# MQTT_SelService_V2.net
KiCad netlist of a schematic drawn in Altium Designer
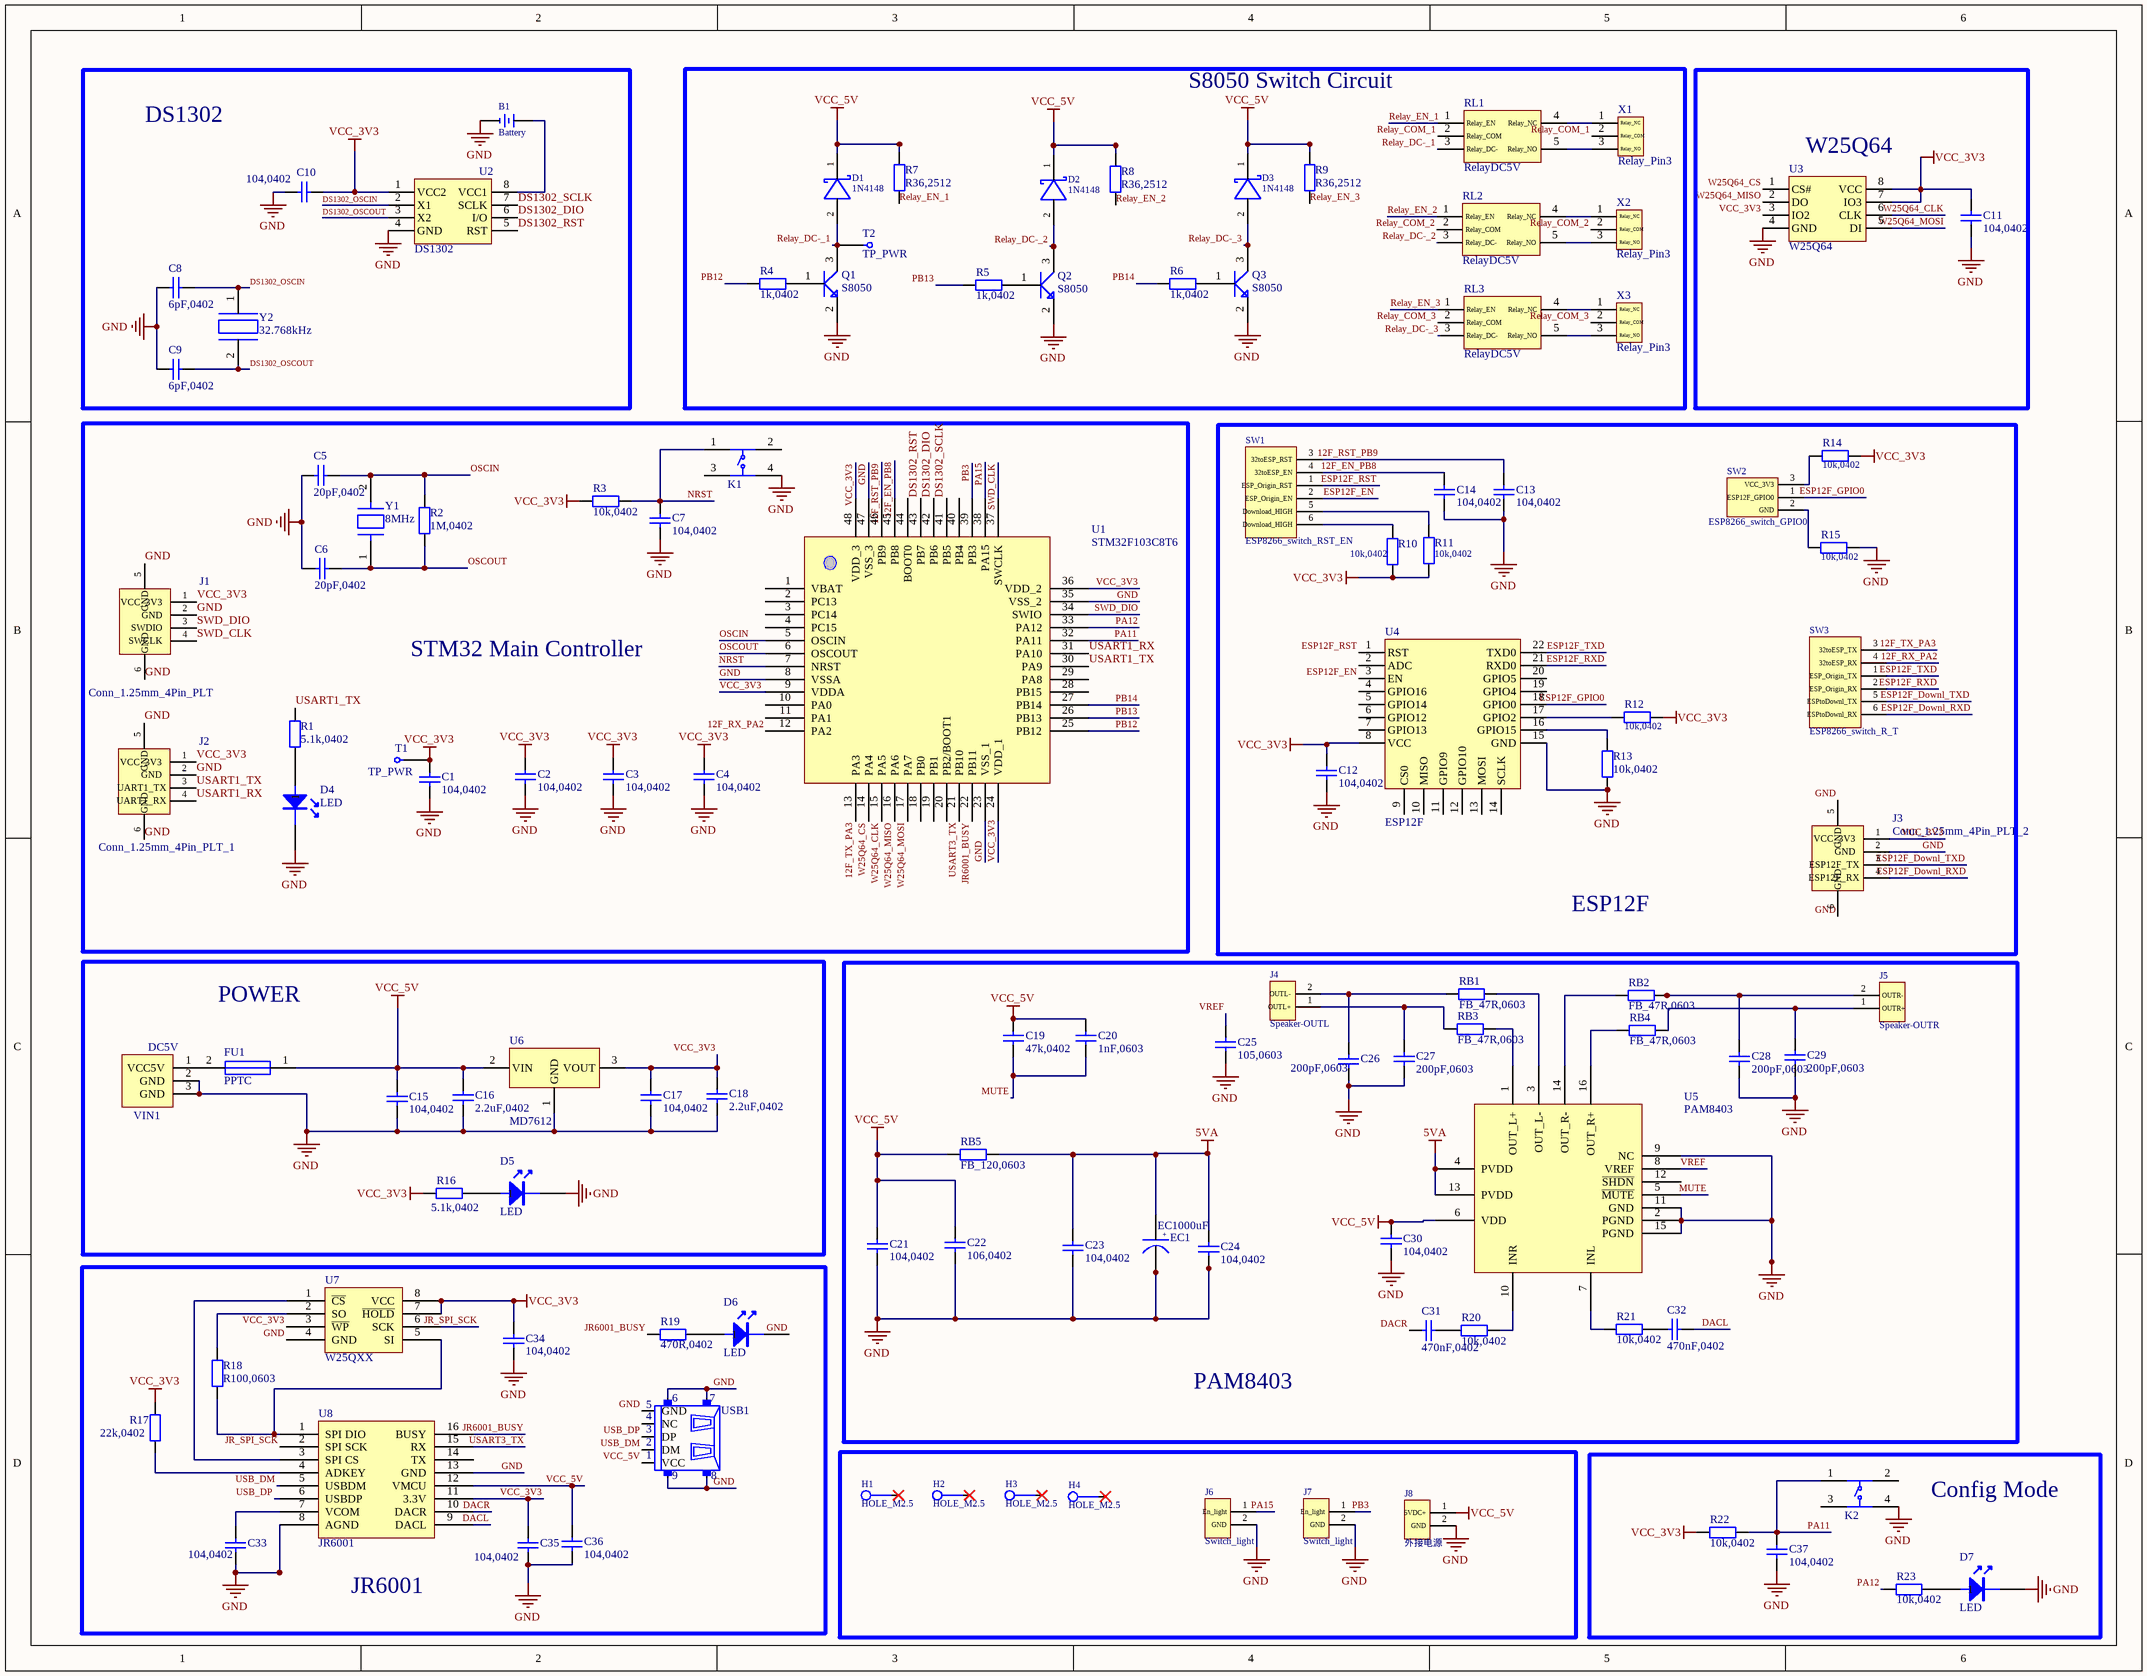
[diagram p0: MQTT_SelService_V2.SchDoc]

(export (version "E")
  (design (tool "Eeschema 10.0.6"))
  (components
    (comp (ref "B1")
      (value "Battery")
      (footprint "Battery")
      (description "V_Backup")
      (libsource (lib "MQTT_SelService_V1") (part "Battery"))
    )
    (comp (ref "C1")
      (value "104,0402")
      (footprint "C0402")
      (fields (field (name "PUBLISHER") "Altium Limited"))
      (libsource (lib "MQTT_SelService_V1") (part "Cap1"))
    )
    (comp (ref "C2")
      (value "104,0402")
      (footprint "C0402")
      (fields (field (name "PUBLISHER") "Altium Limited"))
      (libsource (lib "MQTT_SelService_V1") (part "Cap1"))
    )
    (comp (ref "C3")
      (value "104,0402")
      (footprint "C0402")
      (fields (field (name "PUBLISHER") "Altium Limited"))
      (libsource (lib "MQTT_SelService_V1") (part "Cap1"))
    )
    (comp (ref "C4")
      (value "104,0402")
      (footprint "C0402")
      (fields (field (name "PUBLISHER") "Altium Limited"))
      (libsource (lib "MQTT_SelService_V1") (part "Cap1"))
    )
    (comp (ref "C5")
      (value "20pF,0402")
      (footprint "C0402")
      (fields (field (name "PUBLISHER") "Altium Limited"))
      (libsource (lib "MQTT_SelService_V1") (part "Cap0402_3"))
    )
    (comp (ref "C6")
      (value "20pF,0402")
      (footprint "C0402")
      (fields (field (name "PUBLISHER") "Altium Limited"))
      (libsource (lib "MQTT_SelService_V1") (part "Cap0402_3"))
    )
    (comp (ref "C7")
      (value "104,0402")
      (footprint "C0402")
      (fields (field (name "PUBLISHER") "Altium Limited"))
      (libsource (lib "MQTT_SelService_V1") (part "Cap1"))
    )
    (comp (ref "C8")
      (value "6pF,0402")
      (footprint "C0402")
      (fields (field (name "PUBLISHER") "Altium Limited"))
      (libsource (lib "MQTT_SelService_V1") (part "Cap0402_2"))
    )
    (comp (ref "C9")
      (value "6pF,0402")
      (footprint "C0402")
      (fields (field (name "PUBLISHER") "Altium Limited"))
      (libsource (lib "MQTT_SelService_V1") (part "Cap0402_2"))
    )
    (comp (ref "C10")
      (value "104,0402")
      (footprint "C0402")
      (fields (field (name "PUBLISHER") "Altium Limited"))
      (libsource (lib "MQTT_SelService_V1") (part "Cap1"))
    )
    (comp (ref "C11")
      (value "104,0402")
      (footprint "C0402")
      (fields (field (name "PUBLISHER") "Altium Limited"))
      (libsource (lib "MQTT_SelService_V1") (part "Cap1"))
    )
    (comp (ref "C12")
      (value "104,0402")
      (footprint "C0402")
      (fields (field (name "PUBLISHER") "Altium Limited"))
      (libsource (lib "MQTT_SelService_V1") (part "Cap1"))
    )
    (comp (ref "C13")
      (value "104,0402")
      (footprint "C0402")
      (fields (field (name "PUBLISHER") "Altium Limited"))
      (libsource (lib "MQTT_SelService_V1") (part "Cap1"))
    )
    (comp (ref "C14")
      (value "104,0402")
      (footprint "C0402")
      (fields (field (name "PUBLISHER") "Altium Limited"))
      (libsource (lib "MQTT_SelService_V1") (part "Cap1"))
    )
    (comp (ref "C15")
      (value "104,0402")
      (footprint "C0402")
      (fields (field (name "PUBLISHER") "Altium Limited"))
      (libsource (lib "MQTT_SelService_V1") (part "Cap1"))
    )
    (comp (ref "C16")
      (value "2.2uF,0402")
      (footprint "C0402")
      (fields (field (name "PUBLISHER") "Altium Limited"))
      (libsource (lib "MQTT_SelService_V1") (part "C2.2uF"))
    )
    (comp (ref "C17")
      (value "104,0402")
      (footprint "C0402")
      (fields (field (name "PUBLISHER") "Altium Limited"))
      (libsource (lib "MQTT_SelService_V1") (part "Cap1"))
    )
    (comp (ref "C18")
      (value "2.2uF,0402")
      (footprint "C0402")
      (fields (field (name "PUBLISHER") "Altium Limited"))
      (libsource (lib "MQTT_SelService_V1") (part "C2.2uF"))
    )
    (comp (ref "C19")
      (value "47k,0402")
      (footprint "C0402")
      (description "104,0402")
      (fields (field (name "PUBLISHER") "Altium Limited"))
      (libsource (lib "MQTT_SelService_V1") (part "Cap1"))
    )
    (comp (ref "C20")
      (value "1nF,0603")
      (footprint "C0603")
      (fields (field (name "PUBLISHER") "Altium Limited"))
      (libsource (lib "MQTT_SelService_V1") (part "C1nF"))
    )
    (comp (ref "C21")
      (value "104,0402")
      (footprint "C0402")
      (fields (field (name "PUBLISHER") "Altium Limited"))
      (libsource (lib "MQTT_SelService_V1") (part "Cap1"))
    )
    (comp (ref "C22")
      (value "106,0402")
      (footprint "C0402")
      (description "104,0402")
      (fields (field (name "PUBLISHER") "Altium Limited"))
      (libsource (lib "MQTT_SelService_V1") (part "Cap1"))
    )
    (comp (ref "C23")
      (value "104,0402")
      (footprint "C0402")
      (fields (field (name "PUBLISHER") "Altium Limited"))
      (libsource (lib "MQTT_SelService_V1") (part "Cap1"))
    )
    (comp (ref "C24")
      (value "104,0402")
      (footprint "C0402")
      (fields (field (name "PUBLISHER") "Altium Limited"))
      (libsource (lib "MQTT_SelService_V1") (part "Cap1"))
    )
    (comp (ref "C25")
      (value "105,0603")
      (footprint "C0603")
      (fields (field (name "PUBLISHER") "Altium Limited"))
      (libsource (lib "MQTT_SelService_V1") (part "Cap2"))
    )
    (comp (ref "C26")
      (value "200pF,0603")
      (footprint "C0603")
      (fields (field (name "PUBLISHER") "Altium Limited"))
      (libsource (lib "MQTT_SelService_V1") (part "C200pF"))
    )
    (comp (ref "C27")
      (value "200pF,0603")
      (footprint "C0603")
      (fields (field (name "PUBLISHER") "Altium Limited"))
      (libsource (lib "MQTT_SelService_V1") (part "C200pF"))
    )
    (comp (ref "C28")
      (value "200pF,0603")
      (footprint "C0603")
      (fields (field (name "PUBLISHER") "Altium Limited"))
      (libsource (lib "MQTT_SelService_V1") (part "C200pF"))
    )
    (comp (ref "C29")
      (value "200pF,0603")
      (footprint "C0603")
      (fields (field (name "PUBLISHER") "Altium Limited"))
      (libsource (lib "MQTT_SelService_V1") (part "C200pF"))
    )
    (comp (ref "C30")
      (value "104,0402")
      (footprint "C0402")
      (fields (field (name "PUBLISHER") "Altium Limited"))
      (libsource (lib "MQTT_SelService_V1") (part "Cap1"))
    )
    (comp (ref "C31")
      (value "470nF,0402")
      (footprint "C0402")
      (fields (field (name "PUBLISHER") "Altium Limited"))
      (libsource (lib "MQTT_SelService_V1") (part "C470nF"))
    )
    (comp (ref "C32")
      (value "470nF,0402")
      (footprint "C0402")
      (fields (field (name "PUBLISHER") "Altium Limited"))
      (libsource (lib "MQTT_SelService_V1") (part "C470nF"))
    )
    (comp (ref "C33")
      (value "104,0402")
      (footprint "C0402")
      (fields (field (name "PUBLISHER") "Altium Limited"))
      (libsource (lib "MQTT_SelService_V1") (part "Cap1"))
    )
    (comp (ref "C34")
      (value "104,0402")
      (footprint "C0402")
      (fields (field (name "PUBLISHER") "Altium Limited"))
      (libsource (lib "MQTT_SelService_V1") (part "Cap1"))
    )
    (comp (ref "C35")
      (value "104,0402")
      (footprint "C0402")
      (fields (field (name "PUBLISHER") "Altium Limited"))
      (libsource (lib "MQTT_SelService_V1") (part "Cap1"))
    )
    (comp (ref "C36")
      (value "104,0402")
      (footprint "C0402")
      (fields (field (name "PUBLISHER") "Altium Limited"))
      (libsource (lib "MQTT_SelService_V1") (part "Cap1"))
    )
    (comp (ref "C37")
      (value "104,0402")
      (footprint "C0402")
      (fields (field (name "PUBLISHER") "Altium Limited"))
      (libsource (lib "MQTT_SelService_V1") (part "Cap1"))
    )
    (comp (ref "D1")
      (value "1N4148")
      (footprint "1N4148")
      (description "SOD-123")
      (libsource (lib "MQTT_SelService_V1") (part "1N4148"))
    )
    (comp (ref "D2")
      (value "1N4148")
      (footprint "1N4148")
      (description "SOD-123")
      (libsource (lib "MQTT_SelService_V1") (part "1N4148"))
    )
    (comp (ref "D3")
      (value "1N4148")
      (footprint "1N4148")
      (description "SOD-123")
      (libsource (lib "MQTT_SelService_V1") (part "1N4148"))
    )
    (comp (ref "D4") (value "LED") (footprint "LED0603") (libsource (lib "MQTT_SelService_V1") (part "LED")))
    (comp (ref "D5") (value "LED") (footprint "LED0603") (libsource (lib "MQTT_SelService_V1") (part "LED")))
    (comp (ref "D6") (value "LED") (footprint "LED0603") (libsource (lib "MQTT_SelService_V1") (part "LED")))
    (comp (ref "D7") (value "LED") (footprint "LED0603") (libsource (lib "MQTT_SelService_V1") (part "LED")))
    (comp (ref "EC1")
      (value "EC1000uF")
      (footprint "EC1000uF")
      (description "1000uF")
      (libsource (lib "MQTT_SelService_V1") (part "EC"))
    )
    (comp (ref "FU1") (value "PPTC") (footprint "F0805") (libsource (lib "MQTT_SelService_V1") (part "PPTC")))
    (comp (ref "H1")
      (value "HOLE_M2.5")
      (footprint "hole")
      (libsource (lib "MQTT_SelService_V1") (part "HOLE_M2.5"))
    )
    (comp (ref "H2")
      (value "HOLE_M2.5")
      (footprint "hole")
      (libsource (lib "MQTT_SelService_V1") (part "HOLE_M2.5"))
    )
    (comp (ref "H3")
      (value "HOLE_M2.5")
      (footprint "hole")
      (libsource (lib "MQTT_SelService_V1") (part "HOLE_M2.5"))
    )
    (comp (ref "H4")
      (value "HOLE_M2.5")
      (footprint "hole")
      (libsource (lib "MQTT_SelService_V1") (part "HOLE_M2.5"))
    )
    (comp (ref "J1")
      (value "Conn_1.25mm_4Pin_PLT")
      (footprint "CONN-SMD_4P-P1.25_HCTL_HC-1.25-4PLT")
      (description "SWD_Conn")
      (libsource (lib "MQTT_SelService_V1") (part "Conn_1.25mm_4Pin_PLT"))
    )
    (comp (ref "J2")
      (value "Conn_1.25mm_4Pin_PLT_1")
      (footprint "CONN-SMD_4P-P1.25_HCTL_HC-1.25-4PLT")
      (description "USART_Conn")
      (libsource (lib "MQTT_SelService_V1") (part "Conn_1.25mm_4Pin_PLT_1"))
    )
    (comp (ref "J3")
      (value "Conn_1.25mm_4Pin_PLT_2")
      (footprint "CONN-SMD_4P-P1.25_HCTL_HC-1.25-4PLT")
      (description "ESP_Downl_Conn")
      (libsource (lib "MQTT_SelService_V1") (part "Conn_1.25mm_4Pin_PLT_2"))
    )
    (comp (ref "J4")
      (value "Speaker-OUTL")
      (footprint "XH_2.54mm_2Pin_直插")
      (libsource (lib "MQTT_SelService_V1") (part "Speaker-OUTL"))
    )
    (comp (ref "J5")
      (value "Speaker-OUTR")
      (footprint "XH_2.54mm_2Pin_直插")
      (libsource (lib "MQTT_SelService_V1") (part "Speaker-OUTR"))
    )
    (comp (ref "J6")
      (value "Switch_light")
      (footprint "XH_2.54mm_2Pin_直插")
      (description "2.54mm,直插")
      (libsource (lib "MQTT_SelService_V1") (part "Switch_light"))
    )
    (comp (ref "J7")
      (value "Switch_light")
      (footprint "XH_2.54mm_2Pin_直插")
      (description "2.54mm,直插")
      (libsource (lib "MQTT_SelService_V1") (part "Switch_light"))
    )
    (comp (ref "J8")
      (value "外接电源")
      (footprint "XH_2.54mm_2Pin_直插")
      (description "2.54mm")
      (libsource (lib "MQTT_SelService_V1") (part "外接电源"))
    )
    (comp (ref "K1")
      (value "TS665CJ")
      (footprint "SW-TH_4P-L6.0-W6.0-P4.50-LS6.5")
      (description "矩阵按键")
      (libsource (lib "MQTT_SelService_V1") (part "TS665CJ"))
    )
    (comp (ref "K2")
      (value "TS665CJ")
      (footprint "SW-TH_4P-L6.0-W6.0-P4.50-LS6.5")
      (description "矩阵按键")
      (libsource (lib "MQTT_SelService_V1") (part "TS665CJ"))
    )
    (comp (ref "Q1")
      (value "S8050")
      (footprint "S8050")
      (libsource (lib "MQTT_SelService_V1") (part "S8050"))
    )
    (comp (ref "Q2")
      (value "S8050")
      (footprint "S8050")
      (libsource (lib "MQTT_SelService_V1") (part "S8050"))
    )
    (comp (ref "Q3")
      (value "S8050")
      (footprint "S8050")
      (libsource (lib "MQTT_SelService_V1") (part "S8050"))
    )
    (comp (ref "R1")
      (value "5.1k,0402")
      (footprint "R0402")
      (description "10k,0402")
      (fields (field (name "PUBLISHER") "Altium Limited"))
      (libsource (lib "") (part "R10k_1"))
    )
    (comp (ref "R2")
      (value "1M,0402")
      (footprint "R0402")
      (fields (field (name "PUBLISHER") "Altium Limited"))
      (libsource (lib "MQTT_SelService_V1") (part "R1M"))
    )
    (comp (ref "R3")
      (value "10k,0402")
      (footprint "R0402")
      (description "10,0402")
      (fields (field (name "PUBLISHER") "Altium Limited"))
      (libsource (lib "") (part "R1M_1"))
    )
    (comp (ref "R4")
      (value "1k,0402")
      (footprint "R0402")
      (description "10k,0402")
      (fields (field (name "PUBLISHER") "Altium Limited"))
      (libsource (lib "MQTT_SelService_V1") (part "R10k"))
    )
    (comp (ref "R5")
      (value "1k,0402")
      (footprint "R0402")
      (description "10k,0402")
      (fields (field (name "PUBLISHER") "Altium Limited"))
      (libsource (lib "MQTT_SelService_V1") (part "R10k"))
    )
    (comp (ref "R6")
      (value "1k,0402")
      (footprint "R0402")
      (description "10k,0402")
      (fields (field (name "PUBLISHER") "Altium Limited"))
      (libsource (lib "MQTT_SelService_V1") (part "R10k"))
    )
    (comp (ref "R7")
      (value "R36,2512")
      (footprint "R2512")
      (fields (field (name "PUBLISHER") "Altium Limited"))
      (libsource (lib "MQTT_SelService_V1") (part "R36,2512"))
    )
    (comp (ref "R8")
      (value "R36,2512")
      (footprint "R2512")
      (fields (field (name "PUBLISHER") "Altium Limited"))
      (libsource (lib "MQTT_SelService_V1") (part "R36,2512"))
    )
    (comp (ref "R9")
      (value "R36,2512")
      (footprint "R2512")
      (fields (field (name "PUBLISHER") "Altium Limited"))
      (libsource (lib "MQTT_SelService_V1") (part "R36,2512"))
    )
    (comp (ref "R10")
      (value "10k,0402")
      (footprint "R0402")
      (fields (field (name "PUBLISHER") "Altium Limited"))
      (libsource (lib "") (part "R10k_1"))
    )
    (comp (ref "R11")
      (value "10k,0402")
      (footprint "R0402")
      (fields (field (name "PUBLISHER") "Altium Limited"))
      (libsource (lib "") (part "R10k_1"))
    )
    (comp (ref "R12")
      (value "10k,0402")
      (footprint "R0402")
      (fields (field (name "PUBLISHER") "Altium Limited"))
      (libsource (lib "MQTT_SelService_V1") (part "R10k"))
    )
    (comp (ref "R13")
      (value "10k,0402")
      (footprint "R0402")
      (fields (field (name "PUBLISHER") "Altium Limited"))
      (libsource (lib "") (part "R10k_1"))
    )
    (comp (ref "R14")
      (value "10k,0402")
      (footprint "R0402")
      (fields (field (name "PUBLISHER") "Altium Limited"))
      (libsource (lib "MQTT_SelService_V1") (part "R10k"))
    )
    (comp (ref "R15")
      (value "10k,0402")
      (footprint "R0402")
      (fields (field (name "PUBLISHER") "Altium Limited"))
      (libsource (lib "MQTT_SelService_V1") (part "R10k"))
    )
    (comp (ref "R16")
      (value "5.1k,0402")
      (footprint "R0402")
      (description "10k,0402")
      (fields (field (name "PUBLISHER") "Altium Limited"))
      (libsource (lib "MQTT_SelService_V1") (part "R10k"))
    )
    (comp (ref "R17")
      (value "22k,0402")
      (footprint "R0402")
      (fields (field (name "PUBLISHER") "Altium Limited"))
      (libsource (lib "MQTT_SelService_V1") (part "R22k"))
    )
    (comp (ref "R18")
      (value "R100,0603")
      (footprint "R0603")
      (description "0603")
      (fields (field (name "PUBLISHER") "Altium Limited"))
      (libsource (lib "MQTT_SelService_V1") (part "R100"))
    )
    (comp (ref "R19")
      (value "470R,0402")
      (footprint "R0402")
      (description "10k,0402")
      (fields (field (name "PUBLISHER") "Altium Limited"))
      (libsource (lib "MQTT_SelService_V1") (part "R10k"))
    )
    (comp (ref "R20")
      (value "10k,0402")
      (footprint "R0402")
      (fields (field (name "PUBLISHER") "Altium Limited"))
      (libsource (lib "MQTT_SelService_V1") (part "R10k"))
    )
    (comp (ref "R21")
      (value "10k,0402")
      (footprint "R0402")
      (fields (field (name "PUBLISHER") "Altium Limited"))
      (libsource (lib "MQTT_SelService_V1") (part "R10k"))
    )
    (comp (ref "R22")
      (value "10k,0402")
      (footprint "R0402")
      (description "10,0402")
      (fields (field (name "PUBLISHER") "Altium Limited"))
      (libsource (lib "") (part "R1M_1"))
    )
    (comp (ref "R23")
      (value "10k,0402")
      (footprint "R0402")
      (fields (field (name "PUBLISHER") "Altium Limited"))
      (libsource (lib "MQTT_SelService_V1") (part "R10k"))
    )
    (comp (ref "RB1")
      (value "FB_47R,0603")
      (footprint "R0603")
      (fields (field (name "PUBLISHER") "Altium Limited"))
      (libsource (lib "MQTT_SelService_V1") (part "FB_47R"))
    )
    (comp (ref "RB2")
      (value "FB_47R,0603")
      (footprint "R0603")
      (fields (field (name "PUBLISHER") "Altium Limited"))
      (libsource (lib "MQTT_SelService_V1") (part "FB_47R"))
    )
    (comp (ref "RB3")
      (value "FB_47R,0603")
      (footprint "R0603")
      (fields (field (name "PUBLISHER") "Altium Limited"))
      (libsource (lib "MQTT_SelService_V1") (part "FB_47R"))
    )
    (comp (ref "RB4")
      (value "FB_47R,0603")
      (footprint "R0603")
      (fields (field (name "PUBLISHER") "Altium Limited"))
      (libsource (lib "MQTT_SelService_V1") (part "FB_47R"))
    )
    (comp (ref "RB5")
      (value "FB_120,0603")
      (footprint "R0603")
      (fields (field (name "PUBLISHER") "Altium Limited"))
      (libsource (lib "MQTT_SelService_V1") (part "FB_120"))
    )
    (comp (ref "RL1")
      (value "RelayDC5V")
      (footprint "RelayDC5V")
      (libsource (lib "MQTT_SelService_V1") (part "RelayDC5V"))
    )
    (comp (ref "RL2")
      (value "RelayDC5V")
      (footprint "RelayDC5V")
      (libsource (lib "MQTT_SelService_V1") (part "RelayDC5V"))
    )
    (comp (ref "RL3")
      (value "RelayDC5V")
      (footprint "RelayDC5V")
      (libsource (lib "MQTT_SelService_V1") (part "RelayDC5V"))
    )
    (comp (ref "SW1")
      (value "ESP8266_switch_RST_EN")
      (footprint "switch_TX_RX_toDownload")
      (libsource (lib "MQTT_SelService_V1") (part "ESP8266_switch_RST_EN"))
    )
    (comp (ref "SW2")
      (value "ESP8266_switch_GPIO0")
      (footprint "switch_GPIO0_ESP")
      (libsource (lib "MQTT_SelService_V1") (part "ESP8266_switch_GPIO0"))
    )
    (comp (ref "SW3")
      (value "ESP8266_switch_R_T")
      (footprint "switch_TX_RX_toDownload")
      (libsource (lib "MQTT_SelService_V1") (part "ESP8266_switch_R_T"))
    )
    (comp (ref "T1")
      (value "TP_PWR")
      (footprint "TP_PWR")
      (libsource (lib "MQTT_SelService_V1") (part "TP_PWR"))
    )
    (comp (ref "T2")
      (value "TP_PWR")
      (footprint "TP_PWR")
      (libsource (lib "MQTT_SelService_V1") (part "TP_PWR"))
    )
    (comp (ref "U1")
      (value "STM32F103C8T6")
      (footprint "LQFP-48_L7.0-W7.0-P0.50-LS9.0-BL")
      (libsource (lib "MQTT_SelService_V1") (part "STM32F103C8T6"))
    )
    (comp (ref "U2")
      (value "DS1302")
      (footprint "DS1302")
      (libsource (lib "MQTT_SelService_V1") (part "DS1302"))
    )
    (comp (ref "U3")
      (value "W25Q64")
      (footprint "W25Q64")
      (description "withMaster")
      (libsource (lib "MQTT_SelService_V1") (part "W25Q64"))
    )
    (comp (ref "U4")
      (value "ESP12F")
      (footprint "ESP-12E")
      (libsource (lib "MQTT_SelService_V1") (part "ESP12F"))
    )
    (comp (ref "U5")
      (value "PAM8403")
      (footprint "SO-16")
      (libsource (lib "MQTT_SelService_V1") (part "PAM8403"))
    )
    (comp (ref "U6")
      (value "MD7612")
      (footprint "MD71612A")
      (description "SOT-89")
      (libsource (lib "MQTT_SelService_V1") (part "MD7612A33PA1"))
    )
    (comp (ref "U7")
      (value "W25QXX")
      (footprint "W25Qxx")
      (description "withJR6001")
      (libsource (lib "MQTT_SelService_V1") (part "W25QXX"))
    )
    (comp (ref "U8")
      (value "JR6001")
      (footprint "JR6001")
      (libsource (lib "MQTT_SelService_V1") (part "JR6001"))
    )
    (comp (ref "USB1")
      (value "USB-5PIN")
      (footprint "MICRO-USB-SMD_MICROXNJ")
      (description "withJR6001")
      (libsource (lib "MQTT_SelService_V1") (part "USB-5PIN"))
    )
    (comp (ref "VIN1") (value "DC5V") (footprint "DC5V") (libsource (lib "MQTT_SelService_V1") (part "DC5V")))
    (comp (ref "X1")
      (value "Relay_Pin3")
      (footprint "Relay_Pin3_X")
      (libsource (lib "MQTT_SelService_V1") (part "Relay_Pin3"))
    )
    (comp (ref "X2")
      (value "Relay_Pin3")
      (footprint "Relay_Pin3_X")
      (libsource (lib "MQTT_SelService_V1") (part "Relay_Pin3"))
    )
    (comp (ref "X3")
      (value "Relay_Pin3")
      (footprint "Relay_Pin3_X")
      (libsource (lib "MQTT_SelService_V1") (part "Relay_Pin3"))
    )
    (comp (ref "Y1") (value "8MHz") (footprint "8MHz") (libsource (lib "MQTT_SelService_V1") (part "8MHz")))
    (comp (ref "Y2")
      (value "32.768kHz")
      (footprint "32768Hz")
      (libsource (lib "MQTT_SelService_V1") (part "32.768kHz"))
    )
  )
  (nets
    (net (code "1") (name "/12F_EN_PB8") (class "Default")
      (node (ref "C14") (pin "2") (pinfunction "2_2") (pintype "passive"))
      (node (ref "SW1") (pin "4") (pinfunction "32toESP_EN_4") (pintype "passive"))
      (node (ref "U1") (pin "45") (pinfunction "PB8_45") (pintype "passive"))
    )
    (net (code "2") (name "/12F_RST_PB9") (class "Default")
      (node (ref "C13") (pin "2") (pinfunction "2_2") (pintype "passive"))
      (node (ref "SW1") (pin "3") (pinfunction "32toESP_RST_3") (pintype "passive"))
      (node (ref "U1") (pin "46") (pinfunction "PB9_46") (pintype "passive"))
    )
    (net (code "3") (name "/12F_RX_PA2") (class "Default")
      (node (ref "SW3") (pin "4") (pinfunction "32toESP_RX_4") (pintype "passive"))
      (node (ref "U1") (pin "12") (pinfunction "PA2_12") (pintype "passive"))
    )
    (net (code "4") (name "/12F_TX_PA3") (class "Default")
      (node (ref "SW3") (pin "3") (pinfunction "32toESP_TX_3") (pintype "passive"))
      (node (ref "U1") (pin "13") (pinfunction "PA3_13") (pintype "passive"))
    )
    (net (code "5") (name "/DACL") (class "Default")
      (node (ref "C32") (pin "2") (pinfunction "2_2") (pintype "passive"))
      (node (ref "U8") (pin "9") (pinfunction "DACL_9") (pintype "passive"))
    )
    (net (code "6") (name "/DACR") (class "Default")
      (node (ref "C31") (pin "1") (pinfunction "1_1") (pintype "passive"))
      (node (ref "U8") (pin "10") (pinfunction "DACR_10") (pintype "passive"))
    )
    (net (code "7") (name "/DS1302_DIO") (class "Default")
      (node (ref "U1") (pin "42") (pinfunction "PB6_42") (pintype "passive"))
      (node (ref "U2") (pin "6") (pinfunction "I/O_6") (pintype "passive"))
    )
    (net (code "8") (name "/DS1302_OSCIN") (class "Default")
      (node (ref "C8") (pin "2") (pinfunction "2_2") (pintype "passive"))
      (node (ref "U2") (pin "2") (pinfunction "X1_2") (pintype "passive"))
      (node (ref "Y2") (pin "1") (pinfunction "1_1") (pintype "passive"))
    )
    (net (code "9") (name "/DS1302_OSCOUT") (class "Default")
      (node (ref "C9") (pin "2") (pinfunction "2_2") (pintype "passive"))
      (node (ref "U2") (pin "3") (pinfunction "X2_3") (pintype "passive"))
      (node (ref "Y2") (pin "2") (pinfunction "2_2") (pintype "passive"))
    )
    (net (code "10") (name "/DS1302_RST") (class "Default")
      (node (ref "U1") (pin "43") (pinfunction "PB7_43") (pintype "passive"))
      (node (ref "U2") (pin "5") (pinfunction "RST_5") (pintype "passive"))
    )
    (net (code "11") (name "/DS1302_SCLK") (class "Default")
      (node (ref "U1") (pin "41") (pinfunction "PB5_41") (pintype "passive"))
      (node (ref "U2") (pin "7") (pinfunction "SCLK_7") (pintype "passive"))
    )
    (net (code "12") (name "/ESP12F_Downl_RXD") (class "Default")
      (node (ref "J3") (pin "4") (pinfunction "ESP12F_RX_4") (pintype "passive"))
      (node (ref "SW3") (pin "6") (pinfunction "ESPtoDownl_RX_6") (pintype "passive"))
    )
    (net (code "13") (name "/ESP12F_Downl_TXD") (class "Default")
      (node (ref "J3") (pin "3") (pinfunction "ESP12F_TX_3") (pintype "passive"))
      (node (ref "SW3") (pin "5") (pinfunction "ESPtoDownl_TX_5") (pintype "passive"))
    )
    (net (code "14") (name "/ESP12F_EN") (class "Default")
      (node (ref "SW1") (pin "2") (pinfunction "ESP_Origin_EN_2") (pintype "passive"))
      (node (ref "U4") (pin "3") (pinfunction "EN_3") (pintype "passive"))
    )
    (net (code "15") (name "/ESP12F_GPIO0") (class "Default")
      (node (ref "SW2") (pin "1") (pinfunction "ESP12F_GPIO0_1") (pintype "passive"))
      (node (ref "U4") (pin "18") (pinfunction "GPIO0_18") (pintype "passive"))
    )
    (net (code "16") (name "/ESP12F_RST") (class "Default")
      (node (ref "SW1") (pin "1") (pinfunction "ESP_Origin_RST_1") (pintype "passive"))
      (node (ref "U4") (pin "1") (pinfunction "RST_1") (pintype "passive"))
    )
    (net (code "17") (name "/ESP12F_RXD") (class "Default")
      (node (ref "SW3") (pin "2") (pinfunction "ESP_Origin_RX_2") (pintype "passive"))
      (node (ref "U4") (pin "21") (pinfunction "RXD0_21") (pintype "passive"))
    )
    (net (code "18") (name "/ESP12F_TXD") (class "Default")
      (node (ref "SW3") (pin "1") (pinfunction "ESP_Origin_TX_1") (pintype "passive"))
      (node (ref "U4") (pin "22") (pinfunction "TXD0_22") (pintype "passive"))
    )
    (net (code "19") (name "/JR6001_BUSY") (class "Default")
      (node (ref "R19") (pin "1") (pinfunction "1_1") (pintype "passive"))
      (node (ref "U1") (pin "22") (pinfunction "PB11_22") (pintype "passive"))
      (node (ref "U8") (pin "16") (pinfunction "BUSY_16") (pintype "passive"))
    )
    (net (code "20") (name "/JR_SPI_SCK") (class "Default")
      (node (ref "U7") (pin "6") (pinfunction "SCK_6") (pintype "passive"))
      (node (ref "U8") (pin "2") (pinfunction "SPI_SCK_2") (pintype "passive"))
    )
    (net (code "21") (name "/MUTE") (class "Default")
      (node (ref "C19") (pin "1") (pinfunction "1_1") (pintype "passive"))
      (node (ref "C20") (pin "1") (pinfunction "1_1") (pintype "passive"))
      (node (ref "U5") (pin "5") (pinfunction "~{MUTE}_5") (pintype "passive"))
    )
    (net (code "22") (name "/NRST") (class "Default")
      (node (ref "C7") (pin "2") (pinfunction "2_2") (pintype "passive"))
      (node (ref "K1") (pin "1") (pinfunction "1_1") (pintype "passive"))
      (node (ref "R3") (pin "1") (pinfunction "1_1") (pintype "passive"))
      (node (ref "U1") (pin "7") (pinfunction "NRST_7") (pintype "passive"))
    )
    (net (code "23") (name "/OSCIN") (class "Default")
      (node (ref "C5") (pin "2") (pinfunction "2_2") (pintype "passive"))
      (node (ref "R2") (pin "2") (pinfunction "2_2") (pintype "passive"))
      (node (ref "U1") (pin "5") (pinfunction "OSCIN_5") (pintype "passive"))
      (node (ref "Y1") (pin "2") (pinfunction "2_2") (pintype "passive"))
    )
    (net (code "24") (name "/OSCOUT") (class "Default")
      (node (ref "C6") (pin "2") (pinfunction "2_2") (pintype "passive"))
      (node (ref "R2") (pin "1") (pinfunction "1_1") (pintype "passive"))
      (node (ref "U1") (pin "6") (pinfunction "OSCOUT_6") (pintype "passive"))
      (node (ref "Y1") (pin "1") (pinfunction "1_1") (pintype "passive"))
    )
    (net (code "25") (name "/PA11") (class "Default")
      (node (ref "C37") (pin "2") (pinfunction "2_2") (pintype "passive"))
      (node (ref "K2") (pin "1") (pinfunction "1_1") (pintype "passive"))
      (node (ref "R22") (pin "1") (pinfunction "1_1") (pintype "passive"))
      (node (ref "U1") (pin "32") (pinfunction "PA11_32") (pintype "passive"))
    )
    (net (code "26") (name "/PA12") (class "Default")
      (node (ref "R23") (pin "1") (pinfunction "1_1") (pintype "passive"))
      (node (ref "U1") (pin "33") (pinfunction "PA12_33") (pintype "passive"))
    )
    (net (code "27") (name "/PA15") (class "Default")
      (node (ref "J6") (pin "1") (pinfunction "En_light_1") (pintype "passive"))
      (node (ref "U1") (pin "38") (pinfunction "PA15_38") (pintype "passive"))
    )
    (net (code "28") (name "/PB3") (class "Default")
      (node (ref "J7") (pin "1") (pinfunction "En_light_1") (pintype "passive"))
      (node (ref "U1") (pin "39") (pinfunction "PB3_39") (pintype "passive"))
    )
    (net (code "29") (name "/PB12") (class "Default")
      (node (ref "R4") (pin "1") (pinfunction "1_1") (pintype "passive"))
      (node (ref "U1") (pin "25") (pinfunction "PB12_25") (pintype "passive"))
    )
    (net (code "30") (name "/PB13") (class "Default")
      (node (ref "R5") (pin "1") (pinfunction "1_1") (pintype "passive"))
      (node (ref "U1") (pin "26") (pinfunction "PB13_26") (pintype "passive"))
    )
    (net (code "31") (name "/PB14") (class "Default")
      (node (ref "R6") (pin "1") (pinfunction "1_1") (pintype "passive"))
      (node (ref "U1") (pin "27") (pinfunction "PB14_27") (pintype "passive"))
    )
    (net (code "32") (name "/Relay_COM_1") (class "Default")
      (node (ref "RL1") (pin "2") (pinfunction "Relay_COM_2") (pintype "passive"))
      (node (ref "X1") (pin "2") (pinfunction "Relay_COM_2") (pintype "passive"))
    )
    (net (code "33") (name "/Relay_COM_2") (class "Default")
      (node (ref "RL2") (pin "2") (pinfunction "Relay_COM_2") (pintype "passive"))
      (node (ref "X2") (pin "2") (pinfunction "Relay_COM_2") (pintype "passive"))
    )
    (net (code "34") (name "/Relay_COM_3") (class "Default")
      (node (ref "RL3") (pin "2") (pinfunction "Relay_COM_2") (pintype "passive"))
      (node (ref "X3") (pin "2") (pinfunction "Relay_COM_2") (pintype "passive"))
    )
    (net (code "35") (name "/Relay_DC-_1") (class "Default")
      (node (ref "D1") (pin "2") (pinfunction "2_2") (pintype "passive"))
      (node (ref "Q1") (pin "3") (pinfunction "3_3") (pintype "passive"))
      (node (ref "RL1") (pin "3") (pinfunction "Relay_DC-_3") (pintype "passive"))
      (node (ref "T2") (pin "1") (pinfunction "1_1") (pintype "passive"))
    )
    (net (code "36") (name "/Relay_DC-_2") (class "Default")
      (node (ref "D2") (pin "2") (pinfunction "2_2") (pintype "passive"))
      (node (ref "Q2") (pin "3") (pinfunction "3_3") (pintype "passive"))
      (node (ref "RL2") (pin "3") (pinfunction "Relay_DC-_3") (pintype "passive"))
    )
    (net (code "37") (name "/Relay_DC-_3") (class "Default")
      (node (ref "D3") (pin "2") (pinfunction "2_2") (pintype "passive"))
      (node (ref "Q3") (pin "3") (pinfunction "3_3") (pintype "passive"))
      (node (ref "RL3") (pin "3") (pinfunction "Relay_DC-_3") (pintype "passive"))
    )
    (net (code "38") (name "/Relay_EN_1") (class "Default")
      (node (ref "R7") (pin "1") (pinfunction "1_1") (pintype "passive"))
      (node (ref "RL1") (pin "1") (pinfunction "Relay_EN_1") (pintype "passive"))
    )
    (net (code "39") (name "/Relay_EN_2") (class "Default")
      (node (ref "R8") (pin "1") (pinfunction "1_1") (pintype "passive"))
      (node (ref "RL2") (pin "1") (pinfunction "Relay_EN_1") (pintype "passive"))
    )
    (net (code "40") (name "/Relay_EN_3") (class "Default")
      (node (ref "R9") (pin "1") (pinfunction "1_1") (pintype "passive"))
      (node (ref "RL3") (pin "1") (pinfunction "Relay_EN_1") (pintype "passive"))
    )
    (net (code "41") (name "/SWD_CLK") (class "Default")
      (node (ref "J1") (pin "4") (pinfunction "SWCLK_4") (pintype "passive"))
      (node (ref "U1") (pin "37") (pinfunction "SWCLK_37") (pintype "passive"))
    )
    (net (code "42") (name "/SWD_DIO") (class "Default")
      (node (ref "J1") (pin "3") (pinfunction "SWDIO_3") (pintype "passive"))
      (node (ref "U1") (pin "34") (pinfunction "SWIO_34") (pintype "passive"))
    )
    (net (code "43") (name "/USART1_RX") (class "Default")
      (node (ref "J2") (pin "4") (pinfunction "UART1_RX_4") (pintype "passive"))
      (node (ref "U1") (pin "31") (pinfunction "PA10_31") (pintype "passive"))
    )
    (net (code "44") (name "/USART1_TX") (class "Default")
      (node (ref "J2") (pin "3") (pinfunction "UART1_TX_3") (pintype "passive"))
      (node (ref "R1") (pin "2") (pinfunction "2_2") (pintype "passive"))
      (node (ref "U1") (pin "30") (pinfunction "PA9_30") (pintype "passive"))
    )
    (net (code "45") (name "/USART3_TX") (class "Default")
      (node (ref "U1") (pin "21") (pinfunction "PB10_21") (pintype "passive"))
      (node (ref "U8") (pin "15") (pinfunction "RX_15") (pintype "passive"))
    )
    (net (code "46") (name "/USB_DM") (class "Default")
      (node (ref "U8") (pin "5") (pinfunction "USBDM_5") (pintype "passive"))
      (node (ref "USB1") (pin "2") (pinfunction "DM_2") (pintype "passive"))
    )
    (net (code "47") (name "/USB_DP") (class "Default")
      (node (ref "U8") (pin "6") (pinfunction "USBDP_6") (pintype "passive"))
      (node (ref "USB1") (pin "3") (pinfunction "DP_3") (pintype "passive"))
    )
    (net (code "48") (name "/VREF") (class "Default")
      (node (ref "C25") (pin "2") (pinfunction "2_2") (pintype "passive"))
      (node (ref "U5") (pin "8") (pinfunction "VREF_8") (pintype "passive"))
    )
    (net (code "49") (name "/W25Q64_CLK") (class "Default")
      (node (ref "U1") (pin "15") (pinfunction "PA5_15") (pintype "passive"))
      (node (ref "U3") (pin "6") (pinfunction "CLK_6") (pintype "passive"))
    )
    (net (code "50") (name "/W25Q64_CS") (class "Default")
      (node (ref "U1") (pin "14") (pinfunction "PA4_14") (pintype "passive"))
      (node (ref "U3") (pin "1") (pinfunction "CS#_1") (pintype "passive"))
    )
    (net (code "51") (name "/W25Q64_MISO") (class "Default")
      (node (ref "U1") (pin "16") (pinfunction "PA6_16") (pintype "passive"))
      (node (ref "U3") (pin "2") (pinfunction "DO_2") (pintype "passive"))
    )
    (net (code "52") (name "/W25Q64_MOSI") (class "Default")
      (node (ref "U1") (pin "17") (pinfunction "PA7_17") (pintype "passive"))
      (node (ref "U3") (pin "5") (pinfunction "DI_5") (pintype "passive"))
    )
    (net (code "53") (name "5VA") (class "Default")
      (node (ref "C23") (pin "2") (pinfunction "2_2") (pintype "passive"))
      (node (ref "C24") (pin "2") (pinfunction "2_2") (pintype "passive"))
      (node (ref "EC1") (pin "1") (pinfunction "1_1") (pintype "passive"))
      (node (ref "RB5") (pin "2") (pinfunction "2_2") (pintype "passive"))
      (node (ref "U5") (pin "13") (pinfunction "PVDD_13") (pintype "passive"))
      (node (ref "U5") (pin "4") (pinfunction "PVDD_4") (pintype "passive"))
    )
    (net (code "54") (name "GND") (class "Default")
      (node (ref "B1") (pin "2") (pinfunction "2_2") (pintype "passive"))
      (node (ref "C1") (pin "1") (pinfunction "1_1") (pintype "passive"))
      (node (ref "C10") (pin "1") (pinfunction "1_1") (pintype "passive"))
      (node (ref "C11") (pin "1") (pinfunction "1_1") (pintype "passive"))
      (node (ref "C12") (pin "1") (pinfunction "1_1") (pintype "passive"))
      (node (ref "C13") (pin "1") (pinfunction "1_1") (pintype "passive"))
      (node (ref "C14") (pin "1") (pinfunction "1_1") (pintype "passive"))
      (node (ref "C15") (pin "1") (pinfunction "1_1") (pintype "passive"))
      (node (ref "C16") (pin "1") (pinfunction "1_1") (pintype "passive"))
      (node (ref "C17") (pin "1") (pinfunction "1_1") (pintype "passive"))
      (node (ref "C18") (pin "1") (pinfunction "1_1") (pintype "passive"))
      (node (ref "C2") (pin "1") (pinfunction "1_1") (pintype "passive"))
      (node (ref "C21") (pin "1") (pinfunction "1_1") (pintype "passive"))
      (node (ref "C22") (pin "1") (pinfunction "1_1") (pintype "passive"))
      (node (ref "C23") (pin "1") (pinfunction "1_1") (pintype "passive"))
      (node (ref "C24") (pin "1") (pinfunction "1_1") (pintype "passive"))
      (node (ref "C25") (pin "1") (pinfunction "1_1") (pintype "passive"))
      (node (ref "C26") (pin "1") (pinfunction "1_1") (pintype "passive"))
      (node (ref "C27") (pin "1") (pinfunction "1_1") (pintype "passive"))
      (node (ref "C28") (pin "1") (pinfunction "1_1") (pintype "passive"))
      (node (ref "C29") (pin "1") (pinfunction "1_1") (pintype "passive"))
      (node (ref "C3") (pin "1") (pinfunction "1_1") (pintype "passive"))
      (node (ref "C30") (pin "1") (pinfunction "1_1") (pintype "passive"))
      (node (ref "C33") (pin "2") (pinfunction "2_2") (pintype "passive"))
      (node (ref "C34") (pin "1") (pinfunction "1_1") (pintype "passive"))
      (node (ref "C35") (pin "1") (pinfunction "1_1") (pintype "passive"))
      (node (ref "C36") (pin "1") (pinfunction "1_1") (pintype "passive"))
      (node (ref "C37") (pin "1") (pinfunction "1_1") (pintype "passive"))
      (node (ref "C4") (pin "1") (pinfunction "1_1") (pintype "passive"))
      (node (ref "C5") (pin "1") (pinfunction "1_1") (pintype "passive"))
      (node (ref "C6") (pin "1") (pinfunction "1_1") (pintype "passive"))
      (node (ref "C7") (pin "1") (pinfunction "1_1") (pintype "passive"))
      (node (ref "C8") (pin "1") (pinfunction "1_1") (pintype "passive"))
      (node (ref "C9") (pin "1") (pinfunction "1_1") (pintype "passive"))
      (node (ref "D4") (pin "2") (pinfunction "2_2") (pintype "passive"))
      (node (ref "D5") (pin "2") (pinfunction "2_2") (pintype "passive"))
      (node (ref "D6") (pin "2") (pinfunction "2_2") (pintype "passive"))
      (node (ref "D7") (pin "2") (pinfunction "2_2") (pintype "passive"))
      (node (ref "EC1") (pin "2") (pinfunction "2_2") (pintype "passive"))
      (node (ref "J1") (pin "2") (pinfunction "GND_2") (pintype "passive"))
      (node (ref "J1") (pin "5") (pinfunction "GND_5") (pintype "passive"))
      (node (ref "J1") (pin "6") (pinfunction "GND_6") (pintype "passive"))
      (node (ref "J2") (pin "2") (pinfunction "GND_2") (pintype "passive"))
      (node (ref "J2") (pin "5") (pinfunction "GND_5") (pintype "passive"))
      (node (ref "J2") (pin "6") (pinfunction "GND_6") (pintype "passive"))
      (node (ref "J3") (pin "2") (pinfunction "GND_2") (pintype "passive"))
      (node (ref "J3") (pin "5") (pinfunction "GND_5") (pintype "passive"))
      (node (ref "J3") (pin "6") (pinfunction "GND_6") (pintype "passive"))
      (node (ref "J6") (pin "2") (pinfunction "GND_2") (pintype "passive"))
      (node (ref "J7") (pin "2") (pinfunction "GND_2") (pintype "passive"))
      (node (ref "J8") (pin "2") (pinfunction "GND_2") (pintype "passive"))
      (node (ref "K1") (pin "4") (pinfunction "4_4") (pintype "passive"))
      (node (ref "K2") (pin "4") (pinfunction "4_4") (pintype "passive"))
      (node (ref "Q1") (pin "2") (pinfunction "2_2") (pintype "passive"))
      (node (ref "Q2") (pin "2") (pinfunction "2_2") (pintype "passive"))
      (node (ref "Q3") (pin "2") (pinfunction "2_2") (pintype "passive"))
      (node (ref "R13") (pin "1") (pinfunction "1_1") (pintype "passive"))
      (node (ref "R15") (pin "2") (pinfunction "2_2") (pintype "passive"))
      (node (ref "U1") (pin "23") (pinfunction "VSS_1_23") (pintype "passive"))
      (node (ref "U1") (pin "35") (pinfunction "VSS_2_35") (pintype "passive"))
      (node (ref "U1") (pin "47") (pinfunction "VSS_3_47") (pintype "passive"))
      (node (ref "U1") (pin "8") (pinfunction "VSSA_8") (pintype "passive"))
      (node (ref "U2") (pin "4") (pinfunction "GND_4") (pintype "passive"))
      (node (ref "U3") (pin "4") (pinfunction "GND_4") (pintype "passive"))
      (node (ref "U4") (pin "15") (pinfunction "GND_15") (pintype "passive"))
      (node (ref "U5") (pin "11") (pinfunction "GND_11") (pintype "passive"))
      (node (ref "U5") (pin "15") (pinfunction "PGND_15") (pintype "passive"))
      (node (ref "U5") (pin "2") (pinfunction "PGND_2") (pintype "passive"))
      (node (ref "U5") (pin "9") (pinfunction "NC_9") (pintype "passive"))
      (node (ref "U6") (pin "1") (pinfunction "GND_1") (pintype "passive"))
      (node (ref "U7") (pin "4") (pinfunction "GND_4") (pintype "passive"))
      (node (ref "U8") (pin "13") (pinfunction "GND_13") (pintype "passive"))
      (node (ref "U8") (pin "8") (pinfunction "AGND_8") (pintype "passive"))
      (node (ref "USB1") (pin "5") (pinfunction "GND_5") (pintype "passive"))
      (node (ref "USB1") (pin "6") (pinfunction "6_6") (pintype "passive"))
      (node (ref "USB1") (pin "7") (pinfunction "7_7") (pintype "passive"))
      (node (ref "USB1") (pin "8") (pinfunction "8_8") (pintype "passive"))
      (node (ref "USB1") (pin "9") (pinfunction "9_9") (pintype "passive"))
      (node (ref "VIN1") (pin "2") (pinfunction "GND_2") (pintype "passive"))
      (node (ref "VIN1") (pin "3") (pinfunction "GND_3") (pintype "passive"))
    )
    (net (code "55") (name "Net-(C31-Pad2)") (class "Default")
      (node (ref "C31") (pin "2") (pinfunction "2_2") (pintype "passive"))
      (node (ref "R20") (pin "1") (pinfunction "1_1") (pintype "passive"))
    )
    (net (code "56") (name "Net-(C32-Pad1)") (class "Default")
      (node (ref "C32") (pin "1") (pinfunction "1_1") (pintype "passive"))
      (node (ref "R21") (pin "2") (pinfunction "2_2") (pintype "passive"))
    )
    (net (code "57") (name "Net-(D4-Pad1)") (class "Default")
      (node (ref "D4") (pin "1") (pinfunction "1_1") (pintype "passive"))
      (node (ref "R1") (pin "1") (pinfunction "1_1") (pintype "passive"))
    )
    (net (code "58") (name "Net-(D5-Pad1)") (class "Default")
      (node (ref "D5") (pin "1") (pinfunction "1_1") (pintype "passive"))
      (node (ref "R16") (pin "2") (pinfunction "2_2") (pintype "passive"))
    )
    (net (code "59") (name "Net-(D6-Pad1)") (class "Default")
      (node (ref "D6") (pin "1") (pinfunction "1_1") (pintype "passive"))
      (node (ref "R19") (pin "2") (pinfunction "2_2") (pintype "passive"))
    )
    (net (code "60") (name "Net-(D7-Pad1)") (class "Default")
      (node (ref "D7") (pin "1") (pinfunction "1_1") (pintype "passive"))
      (node (ref "R23") (pin "2") (pinfunction "2_2") (pintype "passive"))
    )
    (net (code "61") (name "Net-(J4-OUTL+)") (class "Default")
      (node (ref "C27") (pin "2") (pinfunction "2_2") (pintype "passive"))
      (node (ref "J4") (pin "1") (pinfunction "OUTL+_1") (pintype "passive"))
      (node (ref "RB3") (pin "1") (pinfunction "1_1") (pintype "passive"))
    )
    (net (code "62") (name "Net-(J4-OUTL-)") (class "Default")
      (node (ref "C26") (pin "2") (pinfunction "2_2") (pintype "passive"))
      (node (ref "J4") (pin "2") (pinfunction "OUTL-_2") (pintype "passive"))
      (node (ref "RB1") (pin "1") (pinfunction "1_1") (pintype "passive"))
    )
    (net (code "63") (name "Net-(J5-OUTR+)") (class "Default")
      (node (ref "C29") (pin "2") (pinfunction "2_2") (pintype "passive"))
      (node (ref "J5") (pin "1") (pinfunction "OUTR+_1") (pintype "passive"))
      (node (ref "RB4") (pin "2") (pinfunction "2_2") (pintype "passive"))
    )
    (net (code "64") (name "Net-(J5-OUTR-)") (class "Default")
      (node (ref "C28") (pin "2") (pinfunction "2_2") (pintype "passive"))
      (node (ref "J5") (pin "2") (pinfunction "OUTR-_2") (pintype "passive"))
      (node (ref "RB2") (pin "2") (pinfunction "2_2") (pintype "passive"))
    )
    (net (code "65") (name "Net-(Q1-Pad1)") (class "Default")
      (node (ref "Q1") (pin "1") (pinfunction "1_1") (pintype "passive"))
      (node (ref "R4") (pin "2") (pinfunction "2_2") (pintype "passive"))
    )
    (net (code "66") (name "Net-(Q2-Pad1)") (class "Default")
      (node (ref "Q2") (pin "1") (pinfunction "1_1") (pintype "passive"))
      (node (ref "R5") (pin "2") (pinfunction "2_2") (pintype "passive"))
    )
    (net (code "67") (name "Net-(Q3-Pad1)") (class "Default")
      (node (ref "Q3") (pin "1") (pinfunction "1_1") (pintype "passive"))
      (node (ref "R6") (pin "2") (pinfunction "2_2") (pintype "passive"))
    )
    (net (code "68") (name "Net-(R10-Pad2)") (class "Default")
      (node (ref "R10") (pin "2") (pinfunction "2_2") (pintype "passive"))
      (node (ref "SW1") (pin "6") (pinfunction "Download_HIGH_6") (pintype "passive"))
    )
    (net (code "69") (name "Net-(R11-Pad2)") (class "Default")
      (node (ref "R11") (pin "2") (pinfunction "2_2") (pintype "passive"))
      (node (ref "SW1") (pin "5") (pinfunction "Download_HIGH_5") (pintype "passive"))
    )
    (net (code "70") (name "Net-(RL1-Relay_NC)") (class "Default")
      (node (ref "RL1") (pin "4") (pinfunction "Relay_NC_4") (pintype "passive"))
      (node (ref "X1") (pin "1") (pinfunction "Relay_NC_1") (pintype "passive"))
    )
    (net (code "71") (name "Net-(RL1-Relay_NO)") (class "Default")
      (node (ref "RL1") (pin "5") (pinfunction "Relay_NO_5") (pintype "passive"))
      (node (ref "X1") (pin "3") (pinfunction "Relay_NO_3") (pintype "passive"))
    )
    (net (code "72") (name "Net-(RL2-Relay_NC)") (class "Default")
      (node (ref "RL2") (pin "4") (pinfunction "Relay_NC_4") (pintype "passive"))
      (node (ref "X2") (pin "1") (pinfunction "Relay_NC_1") (pintype "passive"))
    )
    (net (code "73") (name "Net-(RL2-Relay_NO)") (class "Default")
      (node (ref "RL2") (pin "5") (pinfunction "Relay_NO_5") (pintype "passive"))
      (node (ref "X2") (pin "3") (pinfunction "Relay_NO_3") (pintype "passive"))
    )
    (net (code "74") (name "Net-(RL3-Relay_NC)") (class "Default")
      (node (ref "RL3") (pin "4") (pinfunction "Relay_NC_4") (pintype "passive"))
      (node (ref "X3") (pin "1") (pinfunction "Relay_NC_1") (pintype "passive"))
    )
    (net (code "75") (name "Net-(RL3-Relay_NO)") (class "Default")
      (node (ref "RL3") (pin "5") (pinfunction "Relay_NO_5") (pintype "passive"))
      (node (ref "X3") (pin "3") (pinfunction "Relay_NO_3") (pintype "passive"))
    )
    (net (code "76") (name "Net-(SW2-GND)") (class "Default")
      (node (ref "R15") (pin "1") (pinfunction "1_1") (pintype "passive"))
      (node (ref "SW2") (pin "2") (pinfunction "GND_2") (pintype "passive"))
    )
    (net (code "77") (name "Net-(SW2-VCC_3V3)") (class "Default")
      (node (ref "R14") (pin "1") (pinfunction "1_1") (pintype "passive"))
      (node (ref "SW2") (pin "3") (pinfunction "VCC_3V3_3") (pintype "passive"))
    )
    (net (code "78") (name "Net-(U2-VCC1)") (class "Default")
      (node (ref "B1") (pin "1") (pinfunction "1_1") (pintype "passive"))
      (node (ref "U2") (pin "8") (pinfunction "VCC1_8") (pintype "passive"))
    )
    (net (code "79") (name "Net-(U4-GPIO2)") (class "Default")
      (node (ref "R12") (pin "1") (pinfunction "1_1") (pintype "passive"))
      (node (ref "U4") (pin "17") (pinfunction "GPIO2_17") (pintype "passive"))
    )
    (net (code "80") (name "Net-(U4-GPIO15)") (class "Default")
      (node (ref "R13") (pin "2") (pinfunction "2_2") (pintype "passive"))
      (node (ref "U4") (pin "16") (pinfunction "GPIO15_16") (pintype "passive"))
    )
    (net (code "81") (name "Net-(U5-INL)") (class "Default")
      (node (ref "R21") (pin "1") (pinfunction "1_1") (pintype "passive"))
      (node (ref "U5") (pin "7") (pinfunction "INL_7") (pintype "passive"))
    )
    (net (code "82") (name "Net-(U5-INR)") (class "Default")
      (node (ref "R20") (pin "2") (pinfunction "2_2") (pintype "passive"))
      (node (ref "U5") (pin "10") (pinfunction "INR_10") (pintype "passive"))
    )
    (net (code "83") (name "Net-(U5-OUT_L+)") (class "Default")
      (node (ref "RB3") (pin "2") (pinfunction "2_2") (pintype "passive"))
      (node (ref "U5") (pin "1") (pinfunction "OUT_L+_1") (pintype "passive"))
    )
    (net (code "84") (name "Net-(U5-OUT_L-)") (class "Default")
      (node (ref "RB1") (pin "2") (pinfunction "2_2") (pintype "passive"))
      (node (ref "U5") (pin "3") (pinfunction "OUT_L-_3") (pintype "passive"))
    )
    (net (code "85") (name "Net-(U5-OUT_R+)") (class "Default")
      (node (ref "RB4") (pin "1") (pinfunction "1_1") (pintype "passive"))
      (node (ref "U5") (pin "16") (pinfunction "OUT_R+_16") (pintype "passive"))
    )
    (net (code "86") (name "Net-(U5-OUT_R-)") (class "Default")
      (node (ref "RB2") (pin "1") (pinfunction "1_1") (pintype "passive"))
      (node (ref "U5") (pin "14") (pinfunction "OUT_R-_14") (pintype "passive"))
    )
    (net (code "87") (name "Net-(U7-SI)") (class "Default")
      (node (ref "R18") (pin "1") (pinfunction "1_1") (pintype "passive"))
      (node (ref "U7") (pin "5") (pinfunction "SI_5") (pintype "passive"))
      (node (ref "U8") (pin "1") (pinfunction "SPI_DIO_1") (pintype "passive"))
    )
    (net (code "88") (name "Net-(U7-SO)") (class "Default")
      (node (ref "R18") (pin "2") (pinfunction "2_2") (pintype "passive"))
      (node (ref "U7") (pin "2") (pinfunction "SO_2") (pintype "passive"))
    )
    (net (code "89") (name "Net-(U7-~{CS})") (class "Default")
      (node (ref "U7") (pin "1") (pinfunction "~{CS}_1") (pintype "passive"))
      (node (ref "U8") (pin "3") (pinfunction "SPI_CS_3") (pintype "passive"))
    )
    (net (code "90") (name "Net-(U8-ADKEY)") (class "Default")
      (node (ref "R17") (pin "1") (pinfunction "1_1") (pintype "passive"))
      (node (ref "U8") (pin "4") (pinfunction "ADKEY_4") (pintype "passive"))
    )
    (net (code "91") (name "Net-(U8-VCOM)") (class "Default")
      (node (ref "C33") (pin "1") (pinfunction "1_1") (pintype "passive"))
      (node (ref "U8") (pin "7") (pinfunction "VCOM_7") (pintype "passive"))
    )
    (net (code "92") (name "Net-(VIN1-VCC5V)") (class "Default")
      (node (ref "FU1") (pin "2") (pinfunction "2_2") (pintype "passive"))
      (node (ref "VIN1") (pin "1") (pinfunction "VCC5V_1") (pintype "passive"))
    )
    (net (code "93") (name "VCC_3V3") (class "Default")
      (node (ref "C1") (pin "2") (pinfunction "2_2") (pintype "passive"))
      (node (ref "C10") (pin "2") (pinfunction "2_2") (pintype "passive"))
      (node (ref "C11") (pin "2") (pinfunction "2_2") (pintype "passive"))
      (node (ref "C12") (pin "2") (pinfunction "2_2") (pintype "passive"))
      (node (ref "C17") (pin "2") (pinfunction "2_2") (pintype "passive"))
      (node (ref "C18") (pin "2") (pinfunction "2_2") (pintype "passive"))
      (node (ref "C2") (pin "2") (pinfunction "2_2") (pintype "passive"))
      (node (ref "C3") (pin "2") (pinfunction "2_2") (pintype "passive"))
      (node (ref "C34") (pin "2") (pinfunction "2_2") (pintype "passive"))
      (node (ref "C35") (pin "2") (pinfunction "2_2") (pintype "passive"))
      (node (ref "C4") (pin "2") (pinfunction "2_2") (pintype "passive"))
      (node (ref "J1") (pin "1") (pinfunction "VCC_3V3_1") (pintype "passive"))
      (node (ref "J2") (pin "1") (pinfunction "VCC_3V3_1") (pintype "passive"))
      (node (ref "J3") (pin "1") (pinfunction "VCC_3V3_1") (pintype "passive"))
      (node (ref "R10") (pin "1") (pinfunction "1_1") (pintype "passive"))
      (node (ref "R11") (pin "1") (pinfunction "1_1") (pintype "passive"))
      (node (ref "R12") (pin "2") (pinfunction "2_2") (pintype "passive"))
      (node (ref "R14") (pin "2") (pinfunction "2_2") (pintype "passive"))
      (node (ref "R16") (pin "1") (pinfunction "1_1") (pintype "passive"))
      (node (ref "R17") (pin "2") (pinfunction "2_2") (pintype "passive"))
      (node (ref "R22") (pin "2") (pinfunction "2_2") (pintype "passive"))
      (node (ref "R3") (pin "2") (pinfunction "2_2") (pintype "passive"))
      (node (ref "T1") (pin "1") (pinfunction "1_1") (pintype "passive"))
      (node (ref "U1") (pin "24") (pinfunction "VDD_1_24") (pintype "passive"))
      (node (ref "U1") (pin "36") (pinfunction "VDD_2_36") (pintype "passive"))
      (node (ref "U1") (pin "48") (pinfunction "VDD_3_48") (pintype "passive"))
      (node (ref "U1") (pin "9") (pinfunction "VDDA_9") (pintype "passive"))
      (node (ref "U2") (pin "1") (pinfunction "VCC2_1") (pintype "passive"))
      (node (ref "U3") (pin "3") (pinfunction "IO2_3") (pintype "passive"))
      (node (ref "U3") (pin "7") (pinfunction "IO3_7") (pintype "passive"))
      (node (ref "U3") (pin "8") (pinfunction "VCC_8") (pintype "passive"))
      (node (ref "U4") (pin "8") (pinfunction "VCC_8") (pintype "passive"))
      (node (ref "U6") (pin "3") (pinfunction "VOUT_3") (pintype "passive"))
      (node (ref "U7") (pin "3") (pinfunction "~{WP}_3") (pintype "passive"))
      (node (ref "U7") (pin "7") (pinfunction "~{HOLD}_7") (pintype "passive"))
      (node (ref "U7") (pin "8") (pinfunction "VCC_8") (pintype "passive"))
      (node (ref "U8") (pin "11") (pinfunction "3.3V_11") (pintype "passive"))
    )
    (net (code "94") (name "VCC_5V") (class "Default")
      (node (ref "C15") (pin "2") (pinfunction "2_2") (pintype "passive"))
      (node (ref "C16") (pin "2") (pinfunction "2_2") (pintype "passive"))
      (node (ref "C19") (pin "2") (pinfunction "2_2") (pintype "passive"))
      (node (ref "C20") (pin "2") (pinfunction "2_2") (pintype "passive"))
      (node (ref "C21") (pin "2") (pinfunction "2_2") (pintype "passive"))
      (node (ref "C22") (pin "2") (pinfunction "2_2") (pintype "passive"))
      (node (ref "C30") (pin "2") (pinfunction "2_2") (pintype "passive"))
      (node (ref "C36") (pin "2") (pinfunction "2_2") (pintype "passive"))
      (node (ref "D1") (pin "1") (pinfunction "1_1") (pintype "passive"))
      (node (ref "D2") (pin "1") (pinfunction "1_1") (pintype "passive"))
      (node (ref "D3") (pin "1") (pinfunction "1_1") (pintype "passive"))
      (node (ref "FU1") (pin "1") (pinfunction "1_1") (pintype "passive"))
      (node (ref "J8") (pin "1") (pinfunction "5VDC+_1") (pintype "passive"))
      (node (ref "R7") (pin "2") (pinfunction "2_2") (pintype "passive"))
      (node (ref "R8") (pin "2") (pinfunction "2_2") (pintype "passive"))
      (node (ref "R9") (pin "2") (pinfunction "2_2") (pintype "passive"))
      (node (ref "RB5") (pin "1") (pinfunction "1_1") (pintype "passive"))
      (node (ref "U5") (pin "6") (pinfunction "VDD_6") (pintype "passive"))
      (node (ref "U6") (pin "2") (pinfunction "VIN_2") (pintype "passive"))
      (node (ref "U8") (pin "12") (pinfunction "VMCU_12") (pintype "passive"))
      (node (ref "USB1") (pin "1") (pinfunction "VCC_1") (pintype "passive"))
    )
    (net (code "95") (name "unconnected-(H1-Pad1)") (class "Default")
      (node (ref "H1") (pin "1") (pinfunction "1_1") (pintype "passive"))
    )
    (net (code "96") (name "unconnected-(H2-Pad1)") (class "Default")
      (node (ref "H2") (pin "1") (pinfunction "1_1") (pintype "passive"))
    )
    (net (code "97") (name "unconnected-(H3-Pad1)") (class "Default")
      (node (ref "H3") (pin "1") (pinfunction "1_1") (pintype "passive"))
    )
    (net (code "98") (name "unconnected-(H4-Pad1)") (class "Default")
      (node (ref "H4") (pin "1") (pinfunction "1_1") (pintype "passive"))
    )
    (net (code "99") (name "unconnected-(K1-Pad2)") (class "Default")
      (node (ref "K1") (pin "2") (pinfunction "2_2") (pintype "passive"))
    )
    (net (code "100") (name "unconnected-(K1-Pad3)") (class "Default")
      (node (ref "K1") (pin "3") (pinfunction "3_3") (pintype "passive"))
    )
    (net (code "101") (name "unconnected-(K2-Pad2)") (class "Default")
      (node (ref "K2") (pin "2") (pinfunction "2_2") (pintype "passive"))
    )
    (net (code "102") (name "unconnected-(K2-Pad3)") (class "Default")
      (node (ref "K2") (pin "3") (pinfunction "3_3") (pintype "passive"))
    )
    (net (code "103") (name "unconnected-(U1-BOOT0-Pad44)") (class "Default")
      (node (ref "U1") (pin "44") (pinfunction "BOOT0_44") (pintype "passive"))
    )
    (net (code "104") (name "unconnected-(U1-PA0-Pad10)") (class "Default")
      (node (ref "U1") (pin "10") (pinfunction "PA0_10") (pintype "passive"))
    )
    (net (code "105") (name "unconnected-(U1-PA1-Pad11)") (class "Default")
      (node (ref "U1") (pin "11") (pinfunction "PA1_11") (pintype "passive"))
    )
    (net (code "106") (name "unconnected-(U1-PA8-Pad29)") (class "Default")
      (node (ref "U1") (pin "29") (pinfunction "PA8_29") (pintype "passive"))
    )
    (net (code "107") (name "unconnected-(U1-PB0-Pad18)") (class "Default")
      (node (ref "U1") (pin "18") (pinfunction "PB0_18") (pintype "passive"))
    )
    (net (code "108") (name "unconnected-(U1-PB1-Pad19)") (class "Default")
      (node (ref "U1") (pin "19") (pinfunction "PB1_19") (pintype "passive"))
    )
    (net (code "109") (name "unconnected-(U1-PB2{slash}BOOT1-Pad20)") (class "Default")
      (node (ref "U1") (pin "20") (pinfunction "PB2/BOOT1_20") (pintype "passive"))
    )
    (net (code "110") (name "unconnected-(U1-PB4-Pad40)") (class "Default")
      (node (ref "U1") (pin "40") (pinfunction "PB4_40") (pintype "passive"))
    )
    (net (code "111") (name "unconnected-(U1-PB15-Pad28)") (class "Default")
      (node (ref "U1") (pin "28") (pinfunction "PB15_28") (pintype "passive"))
    )
    (net (code "112") (name "unconnected-(U1-PC13-Pad2)") (class "Default")
      (node (ref "U1") (pin "2") (pinfunction "PC13_2") (pintype "passive"))
    )
    (net (code "113") (name "unconnected-(U1-PC14-Pad3)") (class "Default")
      (node (ref "U1") (pin "3") (pinfunction "PC14_3") (pintype "passive"))
    )
    (net (code "114") (name "unconnected-(U1-PC15-Pad4)") (class "Default")
      (node (ref "U1") (pin "4") (pinfunction "PC15_4") (pintype "passive"))
    )
    (net (code "115") (name "unconnected-(U1-VBAT-Pad1)") (class "Default")
      (node (ref "U1") (pin "1") (pinfunction "VBAT_1") (pintype "passive"))
    )
    (net (code "116") (name "unconnected-(U4-ADC-Pad2)") (class "Default")
      (node (ref "U4") (pin "2") (pinfunction "ADC_2") (pintype "passive"))
    )
    (net (code "117") (name "unconnected-(U4-CS0-Pad9)") (class "Default")
      (node (ref "U4") (pin "9") (pinfunction "CS0_9") (pintype "passive"))
    )
    (net (code "118") (name "unconnected-(U4-GPIO4-Pad19)") (class "Default")
      (node (ref "U4") (pin "19") (pinfunction "GPIO4_19") (pintype "passive"))
    )
    (net (code "119") (name "unconnected-(U4-GPIO5-Pad20)") (class "Default")
      (node (ref "U4") (pin "20") (pinfunction "GPIO5_20") (pintype "passive"))
    )
    (net (code "120") (name "unconnected-(U4-GPIO9-Pad11)") (class "Default")
      (node (ref "U4") (pin "11") (pinfunction "GPIO9_11") (pintype "passive"))
    )
    (net (code "121") (name "unconnected-(U4-GPIO10-Pad12)") (class "Default")
      (node (ref "U4") (pin "12") (pinfunction "GPIO10_12") (pintype "passive"))
    )
    (net (code "122") (name "unconnected-(U4-GPIO12-Pad6)") (class "Default")
      (node (ref "U4") (pin "6") (pinfunction "GPIO12_6") (pintype "passive"))
    )
    (net (code "123") (name "unconnected-(U4-GPIO13-Pad7)") (class "Default")
      (node (ref "U4") (pin "7") (pinfunction "GPIO13_7") (pintype "passive"))
    )
    (net (code "124") (name "unconnected-(U4-GPIO14-Pad5)") (class "Default")
      (node (ref "U4") (pin "5") (pinfunction "GPIO14_5") (pintype "passive"))
    )
    (net (code "125") (name "unconnected-(U4-GPIO16-Pad4)") (class "Default")
      (node (ref "U4") (pin "4") (pinfunction "GPIO16_4") (pintype "passive"))
    )
    (net (code "126") (name "unconnected-(U4-MISO-Pad10)") (class "Default")
      (node (ref "U4") (pin "10") (pinfunction "MISO_10") (pintype "passive"))
    )
    (net (code "127") (name "unconnected-(U4-MOSI-Pad13)") (class "Default")
      (node (ref "U4") (pin "13") (pinfunction "MOSI_13") (pintype "passive"))
    )
    (net (code "128") (name "unconnected-(U4-SCLK-Pad14)") (class "Default")
      (node (ref "U4") (pin "14") (pinfunction "SCLK_14") (pintype "passive"))
    )
    (net (code "129") (name "unconnected-(U5-~{SHDN}-Pad12)") (class "Default")
      (node (ref "U5") (pin "12") (pinfunction "~{SHDN}_12") (pintype "passive"))
    )
    (net (code "130") (name "unconnected-(U8-TX-Pad14)") (class "Default")
      (node (ref "U8") (pin "14") (pinfunction "TX_14") (pintype "passive"))
    )
    (net (code "131") (name "unconnected-(USB1-NC-Pad4)") (class "Default")
      (node (ref "USB1") (pin "4") (pinfunction "NC_4") (pintype "passive"))
    )
  )
)
